# lab1_vodorezov_usb_rs485.net
KiCad netlist of a schematic drawn in Altium Designer
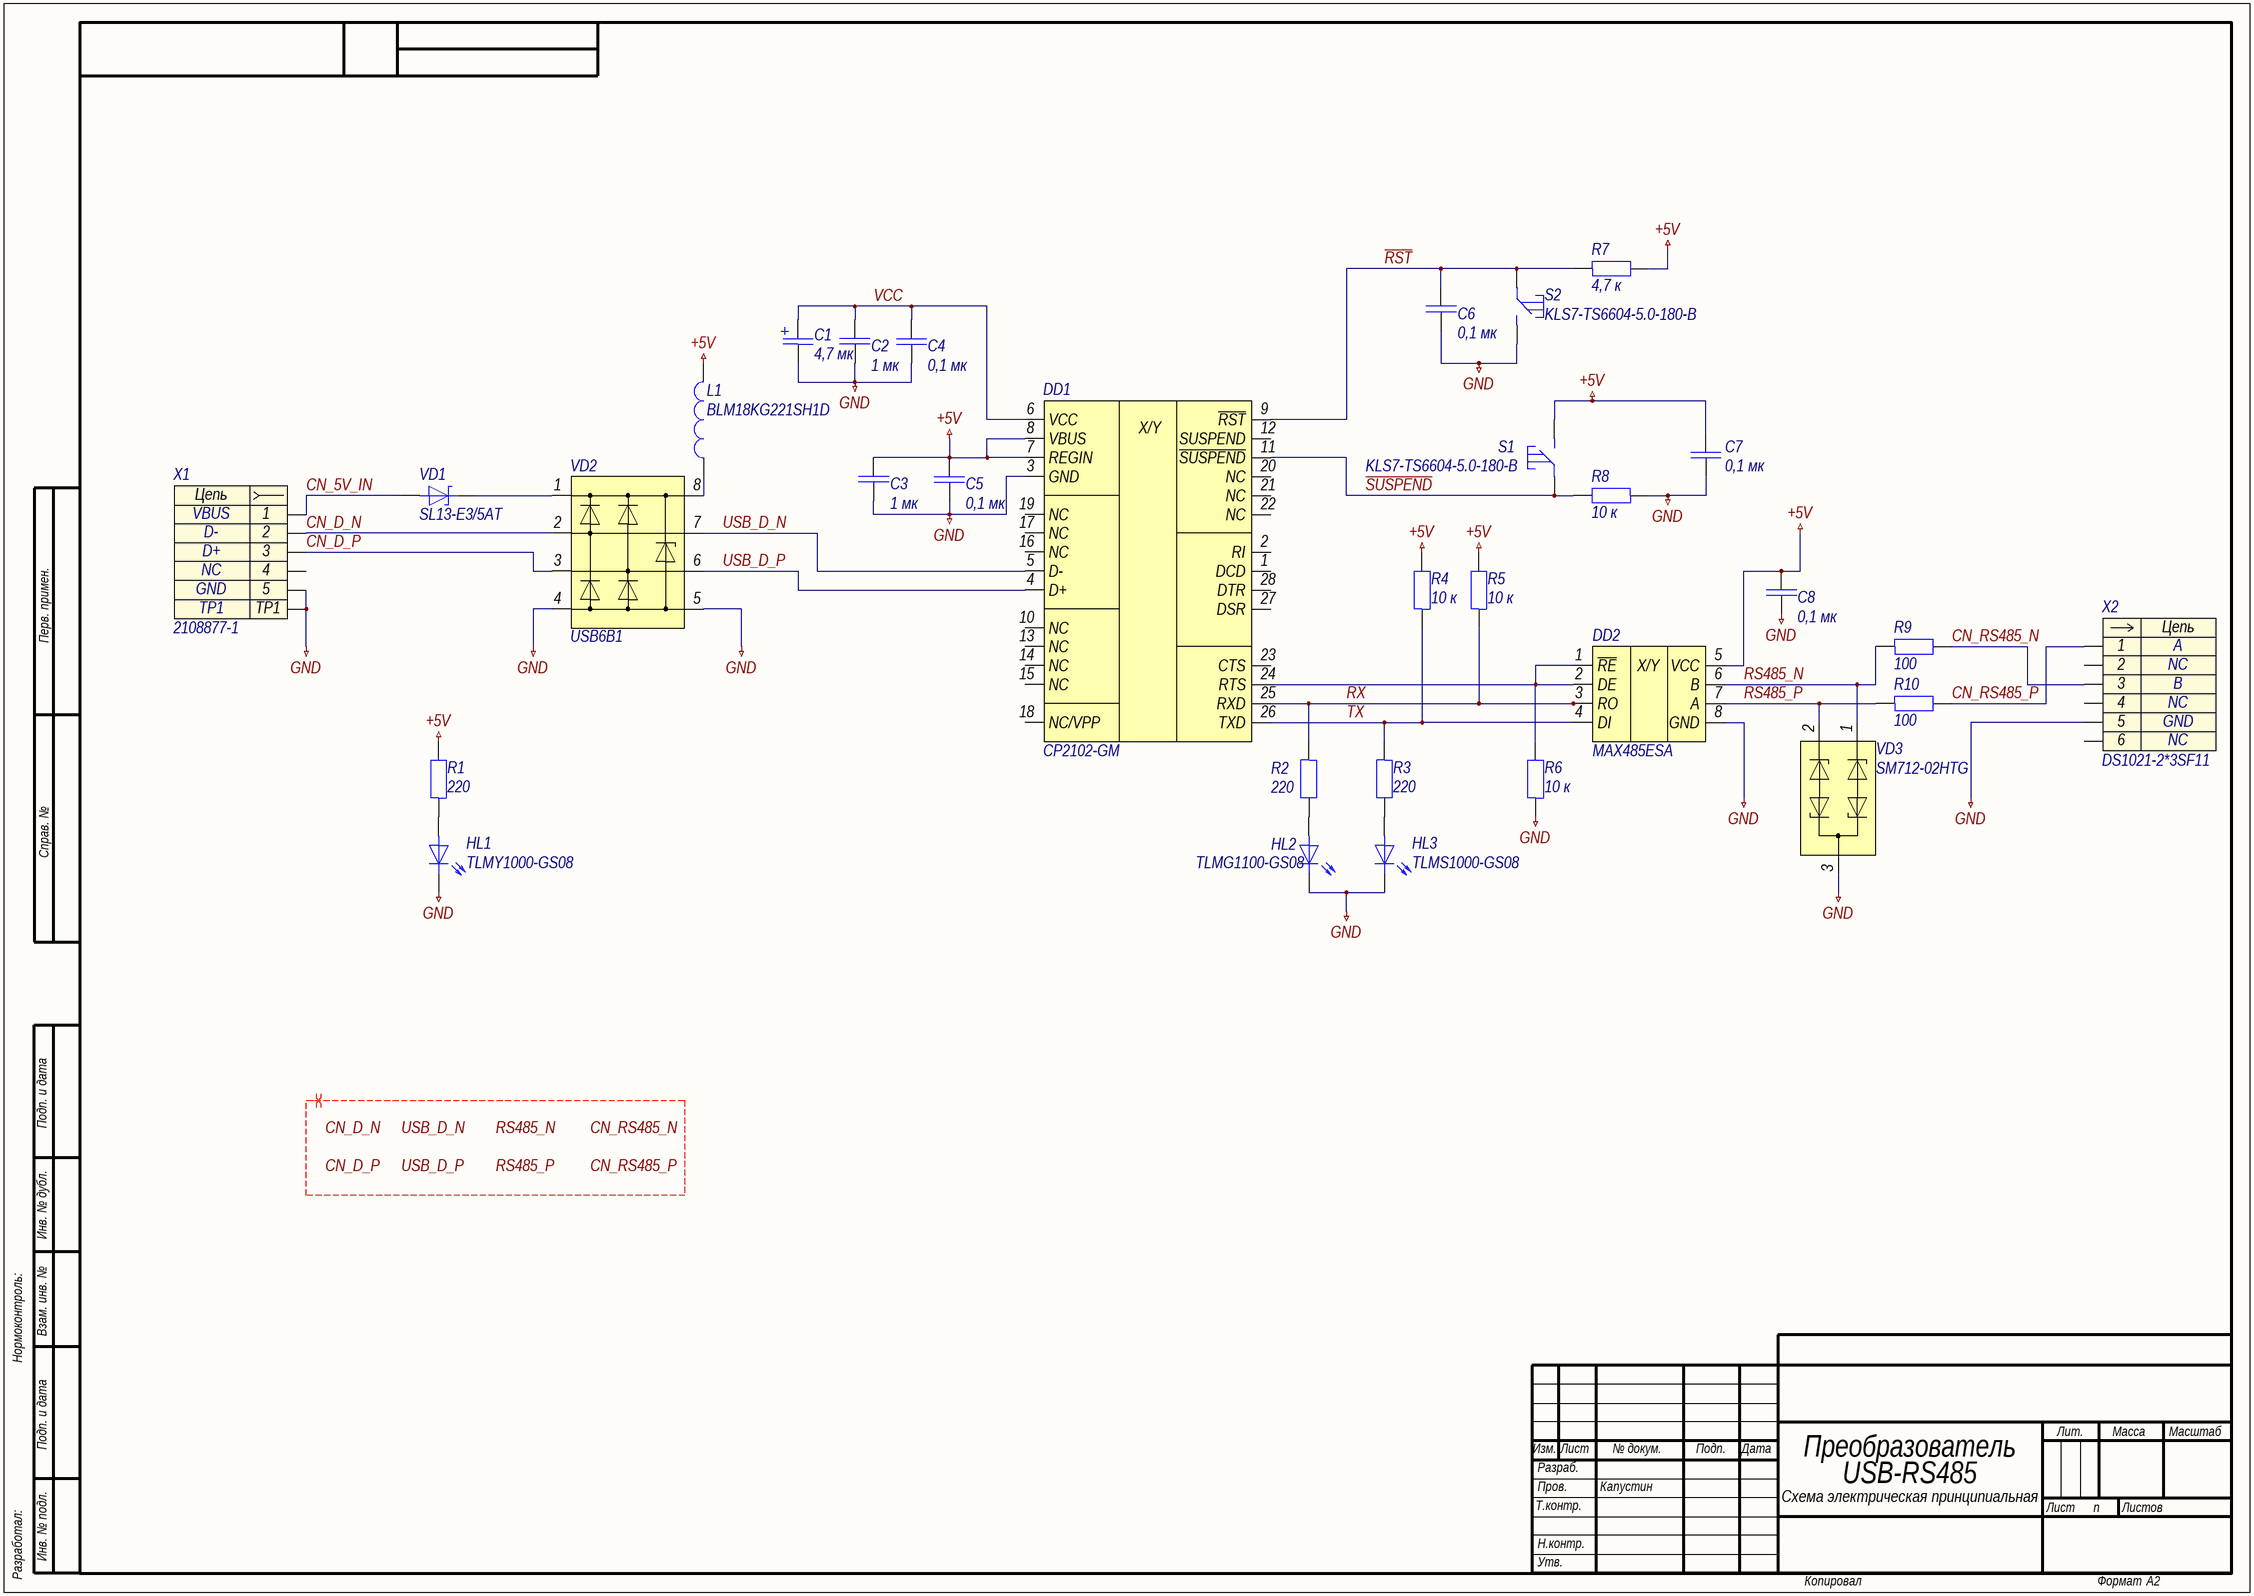
[diagram p0: lab1_vodorezov_usb_rs485.SchDoc]

(export (version "E")
  (design (tool "Eeschema 10.0.6"))
  (components
    (comp (ref "C1")
      (value "4,7 мк")
      (footprint "C1206POLAR")
      (description "=Описание")
      (libsource (lib "Database_Students") (part "C-POLAR"))
    )
    (comp (ref "C2")
      (value "1 мк")
      (footprint "C0603")
      (description "=Описание")
      (libsource (lib "Database_Students") (part "C-NONPOLAR"))
    )
    (comp (ref "C3")
      (value "1 мк")
      (footprint "C0603")
      (description "=Описание")
      (libsource (lib "Database_Students") (part "C-NONPOLAR"))
    )
    (comp (ref "C4")
      (value "0,1 мк")
      (footprint "C0603")
      (description "=Описание")
      (libsource (lib "Database_Students") (part "C-NONPOLAR"))
    )
    (comp (ref "C5")
      (value "0,1 мк")
      (footprint "C0603")
      (description "=Описание")
      (libsource (lib "Database_Students") (part "C-NONPOLAR"))
    )
    (comp (ref "C6")
      (value "0,1 мк")
      (footprint "C0603")
      (description "=Описание")
      (libsource (lib "Database_Students") (part "C-NONPOLAR"))
    )
    (comp (ref "C7")
      (value "0,1 мк")
      (footprint "C0603")
      (description "=Описание")
      (libsource (lib "Database_Students") (part "C-NONPOLAR"))
    )
    (comp (ref "C8")
      (value "0,1 мк")
      (footprint "C0603")
      (description "=Описание")
      (libsource (lib "Database_Students") (part "C-NONPOLAR"))
    )
    (comp (ref "DD1")
      (value "CP2102-GM")
      (footprint "QFN-28")
      (description "=Описание")
      (libsource (lib "Database_Students") (part "CP2102-GM"))
    )
    (comp (ref "DD2")
      (value "MAX485ESA")
      (footprint "SOIC-8")
      (description "=Описание")
      (libsource (lib "Database_Students") (part "MAX485ESA"))
    )
    (comp (ref "HL1")
      (value "TLMY1000-GS08")
      (footprint "HL0603")
      (description "=Описание")
      (libsource (lib "Database_Students") (part "HL-COMMON"))
    )
    (comp (ref "HL2")
      (value "TLMG1100-GS08")
      (footprint "HL0603")
      (description "=Описание")
      (libsource (lib "Database_Students") (part "HL-COMMON"))
    )
    (comp (ref "HL3")
      (value "TLMS1000-GS08")
      (footprint "HL0603")
      (description "=Описание")
      (libsource (lib "Database_Students") (part "HL-COMMON"))
    )
    (comp (ref "L1")
      (value "BLM18KG221SH1D")
      (footprint "BLM-2-0603")
      (description "=Описание")
      (libsource (lib "Database_Students") (part "FERRITE-BEAD"))
    )
    (comp (ref "R1")
      (value "220")
      (footprint "R0603")
      (description "=Описание")
      (libsource (lib "Database_Students") (part "R-COMMON"))
    )
    (comp (ref "R2")
      (value "220")
      (footprint "R0603")
      (description "=Описание")
      (libsource (lib "Database_Students") (part "R-COMMON"))
    )
    (comp (ref "R3")
      (value "220")
      (footprint "R0603")
      (description "=Описание")
      (libsource (lib "Database_Students") (part "R-COMMON"))
    )
    (comp (ref "R4")
      (value "10 к")
      (footprint "R0603")
      (description "=Описание")
      (libsource (lib "Database_Students") (part "R-COMMON"))
    )
    (comp (ref "R5")
      (value "10 к")
      (footprint "R0603")
      (description "=Описание")
      (libsource (lib "Database_Students") (part "R-COMMON"))
    )
    (comp (ref "R6")
      (value "10 к")
      (footprint "R0603")
      (description "=Описание")
      (libsource (lib "Database_Students") (part "R-COMMON"))
    )
    (comp (ref "R7")
      (value "4,7 к")
      (footprint "R0603")
      (description "=Описание")
      (libsource (lib "Database_Students") (part "R-COMMON"))
    )
    (comp (ref "R8")
      (value "10 к")
      (footprint "R0603")
      (description "=Описание")
      (libsource (lib "Database_Students") (part "R-COMMON"))
    )
    (comp (ref "R9")
      (value "100")
      (footprint "R0603")
      (description "=Описание")
      (libsource (lib "Database_Students") (part "R-COMMON"))
    )
    (comp (ref "R10")
      (value "100")
      (footprint "R0603")
      (description "=Описание")
      (libsource (lib "Database_Students") (part "R-COMMON"))
    )
    (comp (ref "S1")
      (value "KLS7-TS6604-5.0-180-B")
      (footprint "button:KLS7-TS6604-5.0-180-B")
      (libsource (lib "button") (part "KLS7-TS6604-5.0-180-B"))
    )
    (comp (ref "S2")
      (value "KLS7-TS6604-5.0-180-B")
      (footprint "button:KLS7-TS6604-5.0-180-B")
      (libsource (lib "button") (part "KLS7-TS6604-5.0-180-B"))
    )
    (comp (ref "VD1")
      (value "SL13-E3/5AT")
      (footprint "DO-214AC")
      (description "=Описание")
      (libsource (lib "Database_Students") (part "DIODE-SCHOTTKY"))
    )
    (comp (ref "VD2")
      (value "USB6B1")
      (footprint "SO-8")
      (description "=Описание")
      (libsource (lib "Database_Students") (part "USB6B1"))
    )
    (comp (ref "VD3")
      (value "SM712-02HTG")
      (footprint "SOT23-3")
      (description "=Описание")
      (libsource (lib "Database_Students") (part "SM712-02HTG"))
    )
    (comp (ref "X1")
      (value "2108877-1")
      (footprint "2108877-1")
      (libsource (lib "Database_Students") (part "HEADER-5-TP1-SCT"))
    )
    (comp (ref "X2")
      (value "DS1021-2*3SF11")
      (footprint "DS1021-2X3SF11")
      (libsource (lib "Database_Students") (part "HEADER-6-PLG"))
    )
  )
  (nets
    (net (code "1") (name "+5V") (class "Default")
      (node (ref "C3") (pin "1") (pinfunction "1_1") (pintype "passive"))
      (node (ref "C5") (pin "2") (pinfunction "2_2") (pintype "passive"))
      (node (ref "C7") (pin "2") (pinfunction "2_2") (pintype "passive"))
      (node (ref "C8") (pin "1") (pinfunction "1_1") (pintype "passive"))
      (node (ref "DD1") (pin "7") (pinfunction "REGIN_7") (pintype "passive"))
      (node (ref "DD1") (pin "8") (pinfunction "VBUS_8") (pintype "passive"))
      (node (ref "DD2") (pin "5") (pinfunction "VCC_5") (pintype "passive"))
      (node (ref "L1") (pin "2") (pinfunction "2_2") (pintype "passive"))
      (node (ref "R1") (pin "2") (pinfunction "2_2") (pintype "passive"))
      (node (ref "R4") (pin "2") (pinfunction "2_2") (pintype "passive"))
      (node (ref "R5") (pin "2") (pinfunction "2_2") (pintype "passive"))
      (node (ref "R7") (pin "2") (pinfunction "2_2") (pintype "passive"))
      (node (ref "S1") (pin "2") (pinfunction "2_2") (pintype "passive"))
    )
    (net (code "2") (name "/CN_5V_IN") (class "Default")
      (node (ref "VD1") (pin "2") (pinfunction "2_2") (pintype "passive"))
      (node (ref "X1") (pin "1") (pinfunction "1_1") (pintype "passive"))
    )
    (net (code "3") (name "/CN_D_N") (class "Default")
      (node (ref "VD2") (pin "2") (pinfunction "2_2") (pintype "passive"))
      (node (ref "X1") (pin "2") (pinfunction "2_2") (pintype "passive"))
    )
    (net (code "4") (name "/CN_D_P") (class "Default")
      (node (ref "VD2") (pin "3") (pinfunction "3_3") (pintype "passive"))
      (node (ref "X1") (pin "3") (pinfunction "3_3") (pintype "passive"))
    )
    (net (code "5") (name "/CN_RS485_N") (class "Default")
      (node (ref "R9") (pin "2") (pinfunction "2_2") (pintype "passive"))
      (node (ref "X2") (pin "3") (pinfunction "3_3") (pintype "passive"))
    )
    (net (code "6") (name "/CN_RS485_P") (class "Default")
      (node (ref "R10") (pin "2") (pinfunction "2_2") (pintype "passive"))
      (node (ref "X2") (pin "1") (pinfunction "1_1") (pintype "passive"))
    )
    (net (code "7") (name "/RS485_N") (class "Default")
      (node (ref "DD2") (pin "6") (pinfunction "B_6") (pintype "passive"))
      (node (ref "R9") (pin "1") (pinfunction "1_1") (pintype "passive"))
      (node (ref "VD3") (pin "1") (pinfunction "1_1") (pintype "passive"))
    )
    (net (code "8") (name "/RS485_P") (class "Default")
      (node (ref "DD2") (pin "7") (pinfunction "A_7") (pintype "passive"))
      (node (ref "R10") (pin "1") (pinfunction "1_1") (pintype "passive"))
      (node (ref "VD3") (pin "2") (pinfunction "2_2") (pintype "passive"))
    )
    (net (code "9") (name "/RX") (class "Default")
      (node (ref "DD1") (pin "25") (pinfunction "RXD_25") (pintype "passive"))
      (node (ref "DD2") (pin "3") (pinfunction "RO_3") (pintype "passive"))
      (node (ref "R2") (pin "1") (pinfunction "1_1") (pintype "passive"))
      (node (ref "R5") (pin "1") (pinfunction "1_1") (pintype "passive"))
    )
    (net (code "10") (name "/TX") (class "Default")
      (node (ref "DD1") (pin "26") (pinfunction "TXD_26") (pintype "passive"))
      (node (ref "DD2") (pin "4") (pinfunction "DI_4") (pintype "passive"))
      (node (ref "R3") (pin "1") (pinfunction "1_1") (pintype "passive"))
      (node (ref "R4") (pin "1") (pinfunction "1_1") (pintype "passive"))
    )
    (net (code "11") (name "/USB_D_N") (class "Default")
      (node (ref "DD1") (pin "5") (pinfunction "D-_5") (pintype "passive"))
      (node (ref "VD2") (pin "7") (pinfunction "7_7") (pintype "passive"))
    )
    (net (code "12") (name "/USB_D_P") (class "Default")
      (node (ref "DD1") (pin "4") (pinfunction "D+_4") (pintype "passive"))
      (node (ref "VD2") (pin "6") (pinfunction "6_6") (pintype "passive"))
    )
    (net (code "13") (name "/VCC") (class "Default")
      (node (ref "C1") (pin "1") (pinfunction "1_1") (pintype "passive"))
      (node (ref "C2") (pin "1") (pinfunction "1_1") (pintype "passive"))
      (node (ref "C4") (pin "2") (pinfunction "2_2") (pintype "passive"))
      (node (ref "DD1") (pin "6") (pinfunction "VCC_6") (pintype "passive"))
    )
    (net (code "14") (name "/~{RST}") (class "Default")
      (node (ref "C6") (pin "1") (pinfunction "1_1") (pintype "passive"))
      (node (ref "DD1") (pin "9") (pinfunction "~{RST}_9") (pintype "passive"))
      (node (ref "R7") (pin "1") (pinfunction "1_1") (pintype "passive"))
      (node (ref "S2") (pin "1") (pinfunction "1_1") (pintype "passive"))
    )
    (net (code "15") (name "/~{SUSPEND}") (class "Default")
      (node (ref "DD1") (pin "11") (pinfunction "~{SUSPEND}_11") (pintype "passive"))
      (node (ref "R8") (pin "2") (pinfunction "2_2") (pintype "passive"))
      (node (ref "S1") (pin "1") (pinfunction "1_1") (pintype "passive"))
    )
    (net (code "16") (name "GND") (class "Default")
      (node (ref "C1") (pin "2") (pinfunction "2_2") (pintype "passive"))
      (node (ref "C2") (pin "2") (pinfunction "2_2") (pintype "passive"))
      (node (ref "C3") (pin "2") (pinfunction "2_2") (pintype "passive"))
      (node (ref "C4") (pin "1") (pinfunction "1_1") (pintype "passive"))
      (node (ref "C5") (pin "1") (pinfunction "1_1") (pintype "passive"))
      (node (ref "C6") (pin "2") (pinfunction "2_2") (pintype "passive"))
      (node (ref "C7") (pin "1") (pinfunction "1_1") (pintype "passive"))
      (node (ref "C8") (pin "2") (pinfunction "2_2") (pintype "passive"))
      (node (ref "DD1") (pin "3") (pinfunction "GND_3") (pintype "passive"))
      (node (ref "DD2") (pin "8") (pinfunction "GND_8") (pintype "passive"))
      (node (ref "HL1") (pin "1") (pinfunction "1_1") (pintype "passive"))
      (node (ref "HL2") (pin "1") (pinfunction "1_1") (pintype "passive"))
      (node (ref "HL3") (pin "1") (pinfunction "1_1") (pintype "passive"))
      (node (ref "R6") (pin "1") (pinfunction "1_1") (pintype "passive"))
      (node (ref "R8") (pin "1") (pinfunction "1_1") (pintype "passive"))
      (node (ref "S2") (pin "2") (pinfunction "2_2") (pintype "passive"))
      (node (ref "VD2") (pin "4") (pinfunction "4_4") (pintype "passive"))
      (node (ref "VD2") (pin "5") (pinfunction "5_5") (pintype "passive"))
      (node (ref "VD3") (pin "3") (pinfunction "3_3") (pintype "passive"))
      (node (ref "X1") (pin "5") (pinfunction "5_5") (pintype "passive"))
      (node (ref "X1") (pin "TP1") (pinfunction "TP1_TP1") (pintype "passive"))
      (node (ref "X2") (pin "5") (pinfunction "5_5") (pintype "passive"))
    )
    (net (code "17") (name "Net-(DD1-RTS)") (class "Default")
      (node (ref "DD1") (pin "24") (pinfunction "RTS_24") (pintype "passive"))
      (node (ref "DD2") (pin "1") (pinfunction "~{RE}_1") (pintype "passive"))
      (node (ref "DD2") (pin "2") (pinfunction "DE_2") (pintype "passive"))
      (node (ref "R6") (pin "2") (pinfunction "2_2") (pintype "passive"))
    )
    (net (code "18") (name "Net-(HL1-Pad2)") (class "Default")
      (node (ref "HL1") (pin "2") (pinfunction "2_2") (pintype "passive"))
      (node (ref "R1") (pin "1") (pinfunction "1_1") (pintype "passive"))
    )
    (net (code "19") (name "Net-(HL2-Pad2)") (class "Default")
      (node (ref "HL2") (pin "2") (pinfunction "2_2") (pintype "passive"))
      (node (ref "R2") (pin "2") (pinfunction "2_2") (pintype "passive"))
    )
    (net (code "20") (name "Net-(HL3-Pad2)") (class "Default")
      (node (ref "HL3") (pin "2") (pinfunction "2_2") (pintype "passive"))
      (node (ref "R3") (pin "2") (pinfunction "2_2") (pintype "passive"))
    )
    (net (code "21") (name "Net-(L1-Pad1)") (class "Default")
      (node (ref "L1") (pin "1") (pinfunction "1_1") (pintype "passive"))
      (node (ref "VD2") (pin "8") (pinfunction "8_8") (pintype "passive"))
    )
    (net (code "22") (name "Net-(VD1-Pad1)") (class "Default")
      (node (ref "VD1") (pin "1") (pinfunction "1_1") (pintype "passive"))
      (node (ref "VD2") (pin "1") (pinfunction "1_1") (pintype "passive"))
    )
    (net (code "23") (name "unconnected-(DD1-CTS-Pad23)") (class "Default")
      (node (ref "DD1") (pin "23") (pinfunction "CTS_23") (pintype "passive"))
    )
    (net (code "24") (name "unconnected-(DD1-DCD-Pad1)") (class "Default")
      (node (ref "DD1") (pin "1") (pinfunction "DCD_1") (pintype "passive"))
    )
    (net (code "25") (name "unconnected-(DD1-DSR-Pad27)") (class "Default")
      (node (ref "DD1") (pin "27") (pinfunction "DSR_27") (pintype "passive"))
    )
    (net (code "26") (name "unconnected-(DD1-DTR-Pad28)") (class "Default")
      (node (ref "DD1") (pin "28") (pinfunction "DTR_28") (pintype "passive"))
    )
    (net (code "27") (name "unconnected-(DD1-NC-Pad10)") (class "Default")
      (node (ref "DD1") (pin "10") (pinfunction "NC_10") (pintype "passive"))
    )
    (net (code "28") (name "unconnected-(DD1-NC-Pad13)") (class "Default")
      (node (ref "DD1") (pin "13") (pinfunction "NC_13") (pintype "passive"))
    )
    (net (code "29") (name "unconnected-(DD1-NC-Pad14)") (class "Default")
      (node (ref "DD1") (pin "14") (pinfunction "NC_14") (pintype "passive"))
    )
    (net (code "30") (name "unconnected-(DD1-NC-Pad15)") (class "Default")
      (node (ref "DD1") (pin "15") (pinfunction "NC_15") (pintype "passive"))
    )
    (net (code "31") (name "unconnected-(DD1-NC-Pad16)") (class "Default")
      (node (ref "DD1") (pin "16") (pinfunction "NC_16") (pintype "passive"))
    )
    (net (code "32") (name "unconnected-(DD1-NC-Pad17)") (class "Default")
      (node (ref "DD1") (pin "17") (pinfunction "NC_17") (pintype "passive"))
    )
    (net (code "33") (name "unconnected-(DD1-NC-Pad19)") (class "Default")
      (node (ref "DD1") (pin "19") (pinfunction "NC_19") (pintype "passive"))
    )
    (net (code "34") (name "unconnected-(DD1-NC-Pad20)") (class "Default")
      (node (ref "DD1") (pin "20") (pinfunction "NC_20") (pintype "passive"))
    )
    (net (code "35") (name "unconnected-(DD1-NC-Pad21)") (class "Default")
      (node (ref "DD1") (pin "21") (pinfunction "NC_21") (pintype "passive"))
    )
    (net (code "36") (name "unconnected-(DD1-NC-Pad22)") (class "Default")
      (node (ref "DD1") (pin "22") (pinfunction "NC_22") (pintype "passive"))
    )
    (net (code "37") (name "unconnected-(DD1-NC{slash}VPP-Pad18)") (class "Default")
      (node (ref "DD1") (pin "18") (pinfunction "NC/VPP_18") (pintype "passive"))
    )
    (net (code "38") (name "unconnected-(DD1-RI-Pad2)") (class "Default")
      (node (ref "DD1") (pin "2") (pinfunction "RI_2") (pintype "passive"))
    )
    (net (code "39") (name "unconnected-(DD1-SUSPEND-Pad12)") (class "Default")
      (node (ref "DD1") (pin "12") (pinfunction "SUSPEND_12") (pintype "passive"))
    )
    (net (code "40") (name "unconnected-(X1-Pad4)") (class "Default")
      (node (ref "X1") (pin "4") (pinfunction "4_4") (pintype "passive"))
    )
    (net (code "41") (name "unconnected-(X2-Pad2)") (class "Default")
      (node (ref "X2") (pin "2") (pinfunction "2_2") (pintype "passive"))
    )
    (net (code "42") (name "unconnected-(X2-Pad4)") (class "Default")
      (node (ref "X2") (pin "4") (pinfunction "4_4") (pintype "passive"))
    )
    (net (code "43") (name "unconnected-(X2-Pad6)") (class "Default")
      (node (ref "X2") (pin "6") (pinfunction "6_6") (pintype "passive"))
    )
  )
)
